# 02_Power.net
KiCad netlist of a schematic drawn in Altium Designer
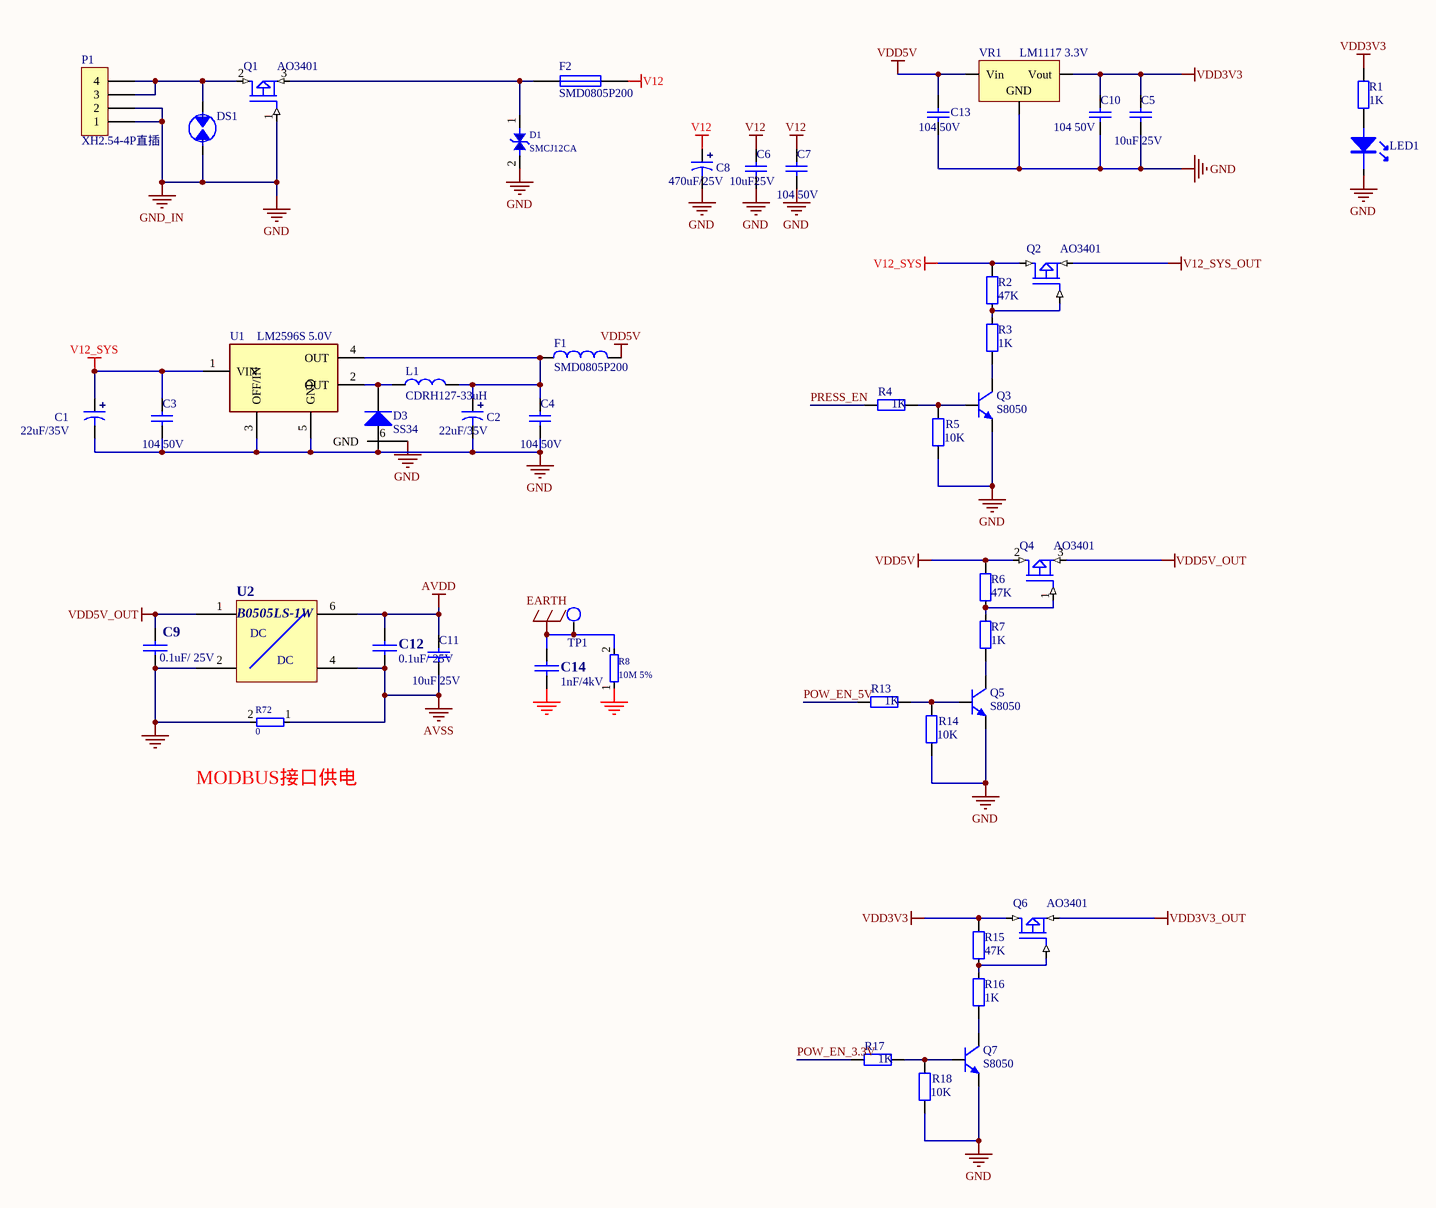
[diagram p0: 02_Power.SchDoc]

(export (version "E")
  (design (tool "Eeschema 10.0.6"))
  (components
    (comp (ref "C1")
      (value "22uF/35V")
      (footprint "1206C")
      (description "电解电容")
      (libsource (lib "XiaoyI") (part "CAP2"))
    )
    (comp (ref "C2")
      (value "22uF/35V")
      (footprint "1206C")
      (description "电解电容")
      (libsource (lib "XiaoyI") (part "CAP2"))
    )
    (comp (ref "C3")
      (value "104 50V")
      (footprint "SMD-0805C")
      (description "贴片电容 10%")
      (libsource (lib "XiaoyI") (part "CAP4"))
    )
    (comp (ref "C4")
      (value "104 50V")
      (footprint "SMD-0805C")
      (description "贴片电容 10%")
      (libsource (lib "XiaoyI") (part "CAP4"))
    )
    (comp (ref "C5")
      (value "10uF 25V")
      (footprint "SMD-0603C")
      (description "贴片电容 20%")
      (libsource (lib "XiaoyI") (part "CAP4"))
    )
    (comp (ref "C6")
      (value "10uF25V")
      (footprint "SMD-0603C")
      (description "贴片电容 20%")
      (libsource (lib "XiaoyI") (part "CAP4"))
    )
    (comp (ref "C7")
      (value "104 50V")
      (footprint "SMD-0603C")
      (description "贴片电容 20%")
      (libsource (lib "XiaoyI") (part "CAP4"))
    )
    (comp (ref "C8")
      (value "470uF/25V")
      (footprint "8*12")
      (description "电解电容")
      (libsource (lib "XiaoyI") (part "CAP2"))
    )
    (comp (ref "C9")
      (value "0.1uF/ 25V")
      (footprint "0603C")
      (description "Capacitor")
      (libsource (lib "*") (part "CAP"))
    )
    (comp (ref "C10")
      (value "104 50V")
      (footprint "SMD-0603C")
      (description "贴片电容 10%")
      (libsource (lib "XiaoyI") (part "CAP4"))
    )
    (comp (ref "C11")
      (value "10uF 25V")
      (footprint "SMD-0603C")
      (description "贴片电容 20%")
      (libsource (lib "XiaoyI") (part "CAP4"))
    )
    (comp (ref "C12")
      (value "0.1uF/ 25V")
      (footprint "0603C")
      (description "Capacitor")
      (libsource (lib "*") (part "CAP"))
    )
    (comp (ref "C13")
      (value "104 50V")
      (footprint "SMD-0603C")
      (description "贴片电容 10%")
      (libsource (lib "XiaoyI") (part "CAP4"))
    )
    (comp (ref "C14")
      (value "1nF/4kV")
      (footprint "CY1")
      (description "Capacitor")
      (libsource (lib "*") (part "CAP"))
    )
    (comp (ref "D1") (value "SMCJ12CA") (footprint "SMC") (libsource (lib "*") (part "D_ESD")))
    (comp (ref "D3") (value "SS34") (footprint "SMA") (libsource (lib "Sch_library") (part "DIODE")))
    (comp (ref "DS1")
      (value "UN1812-90CSMD")
      (footprint "SMD-1812")
      (description "气体放电管 90V")
      (libsource (lib "ABB") (part "DISCHARE-1"))
    )
    (comp (ref "F1")
      (value "SMD0805P200")
      (footprint "0805r")
      (description "Inductor")
      (fields (field (name "PUBLISHER") "Altium Limited"))
      (libsource (lib "Miscellaneous Devices") (part "Inductor"))
    )
    (comp (ref "F2")
      (value "SMD0805P200")
      (footprint "0805R")
      (description "Fuse")
      (fields (field (name "PUBLISHER") "Altium Limited"))
      (libsource (lib "Miscellaneous Devices") (part "Fuse 1"))
    )
    (comp (ref "L1")
      (value "CDRH127-33uH")
      (footprint "CDRH-127")
      (libsource (lib "Sch_library") (part "IND"))
    )
    (comp (ref "LED1")
      (value "蓝光 3528")
      (footprint "SMD-0603D")
      (description "LED 3528 蓝")
      (libsource (lib "XiaoyI") (part "LED0"))
    )
    (comp (ref "P1") (value "XH2.54-4P直插") (footprint "4X2.54MMW") (libsource (lib "ABB") (part "SIP-4")))
    (comp (ref "Q1")
      (value "AO3401")
      (footprint "SOT-23")
      (description "MOSFET P")
      (libsource (lib "") (part "MOSFET P_1"))
    )
    (comp (ref "Q2")
      (value "AO3401")
      (footprint "SOT-23")
      (description "MOSFET P")
      (libsource (lib "ABB") (part "MOSFET P"))
    )
    (comp (ref "Q3")
      (value "S8050")
      (footprint "SOT-23")
      (description "NPN")
      (libsource (lib "XiaoyI") (part "NPN-1"))
    )
    (comp (ref "Q4")
      (value "AO3401")
      (footprint "SOT-23")
      (description "MOSFET P")
      (libsource (lib "") (part "MOSFET P_1"))
    )
    (comp (ref "Q5")
      (value "S8050")
      (footprint "SOT-23")
      (description "NPN")
      (libsource (lib "XiaoyI") (part "NPN-1"))
    )
    (comp (ref "Q6")
      (value "AO3401")
      (footprint "SOT-23")
      (description "MOSFET P")
      (libsource (lib "ABB") (part "MOSFET P"))
    )
    (comp (ref "Q7")
      (value "S8050")
      (footprint "SOT-23")
      (description "NPN")
      (libsource (lib "XiaoyI") (part "NPN-1"))
    )
    (comp (ref "R1")
      (value "1K")
      (footprint "SMD-0603")
      (description "贴片电阻 5%")
      (libsource (lib "XiaoyI") (part "RES2"))
    )
    (comp (ref "R2")
      (value "47K")
      (footprint "SMD-0603")
      (description "贴片电阻 5%")
      (libsource (lib "XiaoyI") (part "RES2"))
    )
    (comp (ref "R3")
      (value "1K")
      (footprint "SMD-0603")
      (description "贴片电阻 5%")
      (libsource (lib "") (part "RES2_2"))
    )
    (comp (ref "R4")
      (value "1K")
      (footprint "SMD-0603")
      (description "贴片电阻 5%")
      (libsource (lib "") (part "RES2_1"))
    )
    (comp (ref "R5")
      (value "10K")
      (footprint "SMD-0603")
      (description "贴片电阻 5%")
      (libsource (lib "") (part "RES2_2"))
    )
    (comp (ref "R6")
      (value "47K")
      (footprint "SMD-0603")
      (description "贴片电阻 5%")
      (libsource (lib "XiaoyI") (part "RES2"))
    )
    (comp (ref "R7")
      (value "1K")
      (footprint "SMD-0603")
      (description "贴片电阻 5%")
      (libsource (lib "") (part "RES2_2"))
    )
    (comp (ref "R8") (value "10M 5%") (footprint "1206r") (libsource (lib "*") (part "RES")))
    (comp (ref "R13")
      (value "1K")
      (footprint "SMD-0603")
      (description "贴片电阻 5%")
      (libsource (lib "") (part "RES2_1"))
    )
    (comp (ref "R14")
      (value "10K")
      (footprint "SMD-0603")
      (description "贴片电阻 5%")
      (libsource (lib "") (part "RES2_2"))
    )
    (comp (ref "R15")
      (value "47K")
      (footprint "SMD-0603")
      (description "贴片电阻 5%")
      (libsource (lib "XiaoyI") (part "RES2"))
    )
    (comp (ref "R16")
      (value "1K")
      (footprint "SMD-0603")
      (description "贴片电阻 5%")
      (libsource (lib "") (part "RES2_2"))
    )
    (comp (ref "R17")
      (value "1K")
      (footprint "SMD-0603")
      (description "贴片电阻 5%")
      (libsource (lib "") (part "RES2_1"))
    )
    (comp (ref "R18")
      (value "10K")
      (footprint "SMD-0603")
      (description "贴片电阻 5%")
      (libsource (lib "") (part "RES2_2"))
    )
    (comp (ref "R72") (value "0") (footprint "1206r") (libsource (lib "*") (part "RES")))
    (comp (ref "TP1") (value "TPS") (footprint "tpd") (libsource (lib "stm32") (part "TPS")))
    (comp (ref "U1")
      (value "LM2596S 5.0V")
      (footprint "TO-263-5")
      (libsource (lib "Sch_library") (part "LM2596"))
    )
    (comp (ref "U2") (value "B0505LS-1W") (footprint "HKSXXXXB-1W") (libsource (lib "*") (part "B0505S")))
    (comp (ref "VR1")
      (value "LM1117 3.3V")
      (footprint "SOT223")
      (description "三端稳压器")
      (libsource (lib "XiaoyI") (part "LM1117"))
    )
  )
  (nets
    (net (code "1") (name "/POW_EN_3.3V") (class "Default")
      (node (ref "R17") (pin "1") (pinfunction "1_1") (pintype "passive"))
    )
    (net (code "2") (name "/POW_EN_5V") (class "Default")
      (node (ref "R13") (pin "1") (pinfunction "1_1") (pintype "passive"))
    )
    (net (code "3") (name "/PRESS_EN") (class "Default")
      (node (ref "R4") (pin "1") (pinfunction "1_1") (pintype "passive"))
    )
    (net (code "4") (name "AVDD") (class "Default")
      (node (ref "C11") (pin "2") (pinfunction "2_2") (pintype "passive"))
      (node (ref "C12") (pin "1") (pinfunction "1_1") (pintype "passive"))
      (node (ref "U2") (pin "6") (pintype "passive"))
    )
    (net (code "5") (name "AVSS") (class "Default")
      (node (ref "C11") (pin "1") (pinfunction "1_1") (pintype "passive"))
      (node (ref "C12") (pin "2") (pinfunction "2_2") (pintype "passive"))
      (node (ref "R72") (pin "1") (pinfunction "1_1") (pintype "passive"))
      (node (ref "U2") (pin "4") (pintype "passive"))
    )
    (net (code "6") (name "EARTH") (class "Default")
      (node (ref "C14") (pin "1") (pinfunction "1_1") (pintype "passive"))
      (node (ref "R8") (pin "2") (pinfunction "2_2") (pintype "passive"))
      (node (ref "TP1") (pin "1") (pinfunction "1_1") (pintype "passive"))
    )
    (net (code "7") (name "GND") (class "Default")
      (node (ref "C1") (pin "2") (pinfunction "2_2") (pintype "passive"))
      (node (ref "C10") (pin "1") (pinfunction "1_1") (pintype "passive"))
      (node (ref "C13") (pin "1") (pinfunction "1_1") (pintype "passive"))
      (node (ref "C14") (pin "2") (pinfunction "2_2") (pintype "passive"))
      (node (ref "C2") (pin "2") (pinfunction "2_2") (pintype "passive"))
      (node (ref "C3") (pin "1") (pinfunction "1_1") (pintype "passive"))
      (node (ref "C4") (pin "1") (pinfunction "1_1") (pintype "passive"))
      (node (ref "C5") (pin "1") (pinfunction "1_1") (pintype "passive"))
      (node (ref "C6") (pin "1") (pinfunction "1_1") (pintype "passive"))
      (node (ref "C7") (pin "1") (pinfunction "1_1") (pintype "passive"))
      (node (ref "C8") (pin "2") (pinfunction "2_2") (pintype "passive"))
      (node (ref "C9") (pin "2") (pinfunction "2_2") (pintype "passive"))
      (node (ref "D1") (pin "2") (pintype "passive"))
      (node (ref "D3") (pin "1") (pinfunction "A_1") (pintype "passive"))
      (node (ref "DS1") (pin "2") (pinfunction "2_2") (pintype "passive"))
      (node (ref "LED1") (pin "2") (pinfunction "2_2") (pintype "passive"))
      (node (ref "P1") (pin "1") (pinfunction "1_1") (pintype "passive"))
      (node (ref "P1") (pin "2") (pinfunction "2_2") (pintype "passive"))
      (node (ref "Q1") (pin "1") (pinfunction "G_1") (pintype "input"))
      (node (ref "Q3") (pin "2") (pinfunction "E_2") (pintype "passive"))
      (node (ref "Q5") (pin "2") (pinfunction "E_2") (pintype "passive"))
      (node (ref "Q7") (pin "2") (pinfunction "E_2") (pintype "passive"))
      (node (ref "R14") (pin "1") (pinfunction "1_1") (pintype "passive"))
      (node (ref "R18") (pin "1") (pinfunction "1_1") (pintype "passive"))
      (node (ref "R5") (pin "1") (pinfunction "1_1") (pintype "passive"))
      (node (ref "R72") (pin "2") (pinfunction "2_2") (pintype "passive"))
      (node (ref "R8") (pin "1") (pinfunction "1_1") (pintype "passive"))
      (node (ref "U1") (pin "3") (pinfunction "OFF/IN_3") (pintype "passive"))
      (node (ref "U1") (pin "5") (pinfunction "GND_5") (pintype "passive"))
      (node (ref "U1") (pin "6") (pinfunction "GND_6") (pintype "passive"))
      (node (ref "U2") (pin "2") (pintype "passive"))
      (node (ref "VR1") (pin "1") (pinfunction "GND_1") (pintype "passive"))
    )
    (net (code "8") (name "Net-(C2-Pad1)") (class "Default")
      (node (ref "C2") (pin "1") (pinfunction "1_1") (pintype "passive"))
      (node (ref "C4") (pin "2") (pinfunction "2_2") (pintype "passive"))
      (node (ref "F1") (pin "1") (pinfunction "1_1") (pintype "passive"))
      (node (ref "L1") (pin "2") (pinfunction "2_2") (pintype "passive"))
      (node (ref "U1") (pin "4") (pinfunction "OUT_4") (pintype "passive"))
    )
    (net (code "9") (name "Net-(D3-K)") (class "Default")
      (node (ref "D3") (pin "2") (pinfunction "K_2") (pintype "passive"))
      (node (ref "L1") (pin "1") (pinfunction "1_1") (pintype "passive"))
      (node (ref "U1") (pin "2") (pinfunction "OUT_2") (pintype "passive"))
    )
    (net (code "10") (name "Net-(LED1-Pad1)") (class "Default")
      (node (ref "LED1") (pin "1") (pinfunction "1_1") (pintype "passive"))
      (node (ref "R1") (pin "2") (pinfunction "2_2") (pintype "passive"))
    )
    (net (code "11") (name "Net-(Q1-D)") (class "Default")
      (node (ref "DS1") (pin "1") (pinfunction "1_1") (pintype "passive"))
      (node (ref "P1") (pin "3") (pinfunction "3_3") (pintype "passive"))
      (node (ref "P1") (pin "4") (pinfunction "4_4") (pintype "passive"))
      (node (ref "Q1") (pin "2") (pinfunction "D_2") (pintype "input"))
    )
    (net (code "12") (name "Net-(Q1-S)") (class "Default")
      (node (ref "D1") (pin "1") (pintype "passive"))
      (node (ref "F2") (pin "1") (pinfunction "1_1") (pintype "passive"))
      (node (ref "Q1") (pin "3") (pinfunction "S_3") (pintype "input"))
    )
    (net (code "13") (name "Net-(Q2-G)") (class "Default")
      (node (ref "Q2") (pin "1") (pinfunction "G_1") (pintype "input"))
      (node (ref "R2") (pin "2") (pinfunction "2_2") (pintype "passive"))
      (node (ref "R3") (pin "2") (pinfunction "2_2") (pintype "passive"))
    )
    (net (code "14") (name "Net-(Q3-B)") (class "Default")
      (node (ref "Q3") (pin "1") (pinfunction "B_1") (pintype "passive"))
      (node (ref "R4") (pin "2") (pinfunction "2_2") (pintype "passive"))
      (node (ref "R5") (pin "2") (pinfunction "2_2") (pintype "passive"))
    )
    (net (code "15") (name "Net-(Q3-C)") (class "Default")
      (node (ref "Q3") (pin "3") (pinfunction "C_3") (pintype "passive"))
      (node (ref "R3") (pin "1") (pinfunction "1_1") (pintype "passive"))
    )
    (net (code "16") (name "Net-(Q4-G)") (class "Default")
      (node (ref "Q4") (pin "1") (pinfunction "G_1") (pintype "input"))
      (node (ref "R6") (pin "2") (pinfunction "2_2") (pintype "passive"))
      (node (ref "R7") (pin "2") (pinfunction "2_2") (pintype "passive"))
    )
    (net (code "17") (name "Net-(Q5-B)") (class "Default")
      (node (ref "Q5") (pin "1") (pinfunction "B_1") (pintype "passive"))
      (node (ref "R13") (pin "2") (pinfunction "2_2") (pintype "passive"))
      (node (ref "R14") (pin "2") (pinfunction "2_2") (pintype "passive"))
    )
    (net (code "18") (name "Net-(Q5-C)") (class "Default")
      (node (ref "Q5") (pin "3") (pinfunction "C_3") (pintype "passive"))
      (node (ref "R7") (pin "1") (pinfunction "1_1") (pintype "passive"))
    )
    (net (code "19") (name "Net-(Q6-G)") (class "Default")
      (node (ref "Q6") (pin "1") (pinfunction "G_1") (pintype "input"))
      (node (ref "R15") (pin "2") (pinfunction "2_2") (pintype "passive"))
      (node (ref "R16") (pin "2") (pinfunction "2_2") (pintype "passive"))
    )
    (net (code "20") (name "Net-(Q7-B)") (class "Default")
      (node (ref "Q7") (pin "1") (pinfunction "B_1") (pintype "passive"))
      (node (ref "R17") (pin "2") (pinfunction "2_2") (pintype "passive"))
      (node (ref "R18") (pin "2") (pinfunction "2_2") (pintype "passive"))
    )
    (net (code "21") (name "Net-(Q7-C)") (class "Default")
      (node (ref "Q7") (pin "3") (pinfunction "C_3") (pintype "passive"))
      (node (ref "R16") (pin "1") (pinfunction "1_1") (pintype "passive"))
    )
    (net (code "22") (name "V12") (class "Default")
      (node (ref "C6") (pin "2") (pinfunction "2_2") (pintype "passive"))
      (node (ref "C7") (pin "2") (pinfunction "2_2") (pintype "passive"))
      (node (ref "C8") (pin "1") (pinfunction "1_1") (pintype "passive"))
      (node (ref "F2") (pin "2") (pinfunction "2_2") (pintype "passive"))
    )
    (net (code "23") (name "V12_SYS") (class "Default")
      (node (ref "C1") (pin "1") (pinfunction "1_1") (pintype "passive"))
      (node (ref "C3") (pin "2") (pinfunction "2_2") (pintype "passive"))
      (node (ref "Q2") (pin "2") (pinfunction "D_2") (pintype "input"))
      (node (ref "R2") (pin "1") (pinfunction "1_1") (pintype "passive"))
      (node (ref "U1") (pin "1") (pinfunction "VIN_1") (pintype "passive"))
    )
    (net (code "24") (name "V12_SYS_OUT") (class "Default")
      (node (ref "Q2") (pin "3") (pinfunction "S_3") (pintype "input"))
    )
    (net (code "25") (name "VDD3V3") (class "Default")
      (node (ref "C10") (pin "2") (pinfunction "2_2") (pintype "passive"))
      (node (ref "C5") (pin "2") (pinfunction "2_2") (pintype "passive"))
      (node (ref "Q6") (pin "2") (pinfunction "D_2") (pintype "input"))
      (node (ref "R1") (pin "1") (pinfunction "1_1") (pintype "passive"))
      (node (ref "R15") (pin "1") (pinfunction "1_1") (pintype "passive"))
      (node (ref "VR1") (pin "2") (pinfunction "Vout_2") (pintype "passive"))
    )
    (net (code "26") (name "VDD3V3_OUT") (class "Default")
      (node (ref "Q6") (pin "3") (pinfunction "S_3") (pintype "input"))
    )
    (net (code "27") (name "VDD5V") (class "Default")
      (node (ref "C13") (pin "2") (pinfunction "2_2") (pintype "passive"))
      (node (ref "F1") (pin "2") (pinfunction "2_2") (pintype "passive"))
      (node (ref "Q4") (pin "2") (pinfunction "D_2") (pintype "input"))
      (node (ref "R6") (pin "1") (pinfunction "1_1") (pintype "passive"))
      (node (ref "VR1") (pin "3") (pinfunction "Vin_3") (pintype "passive"))
    )
    (net (code "28") (name "VDD5V_OUT") (class "Default")
      (node (ref "C9") (pin "1") (pinfunction "1_1") (pintype "passive"))
      (node (ref "Q4") (pin "3") (pinfunction "S_3") (pintype "input"))
      (node (ref "U2") (pin "1") (pintype "passive"))
    )
  )
)
